# CH1_ANALOG.net
KiCad netlist of a schematic drawn in Altium Designer
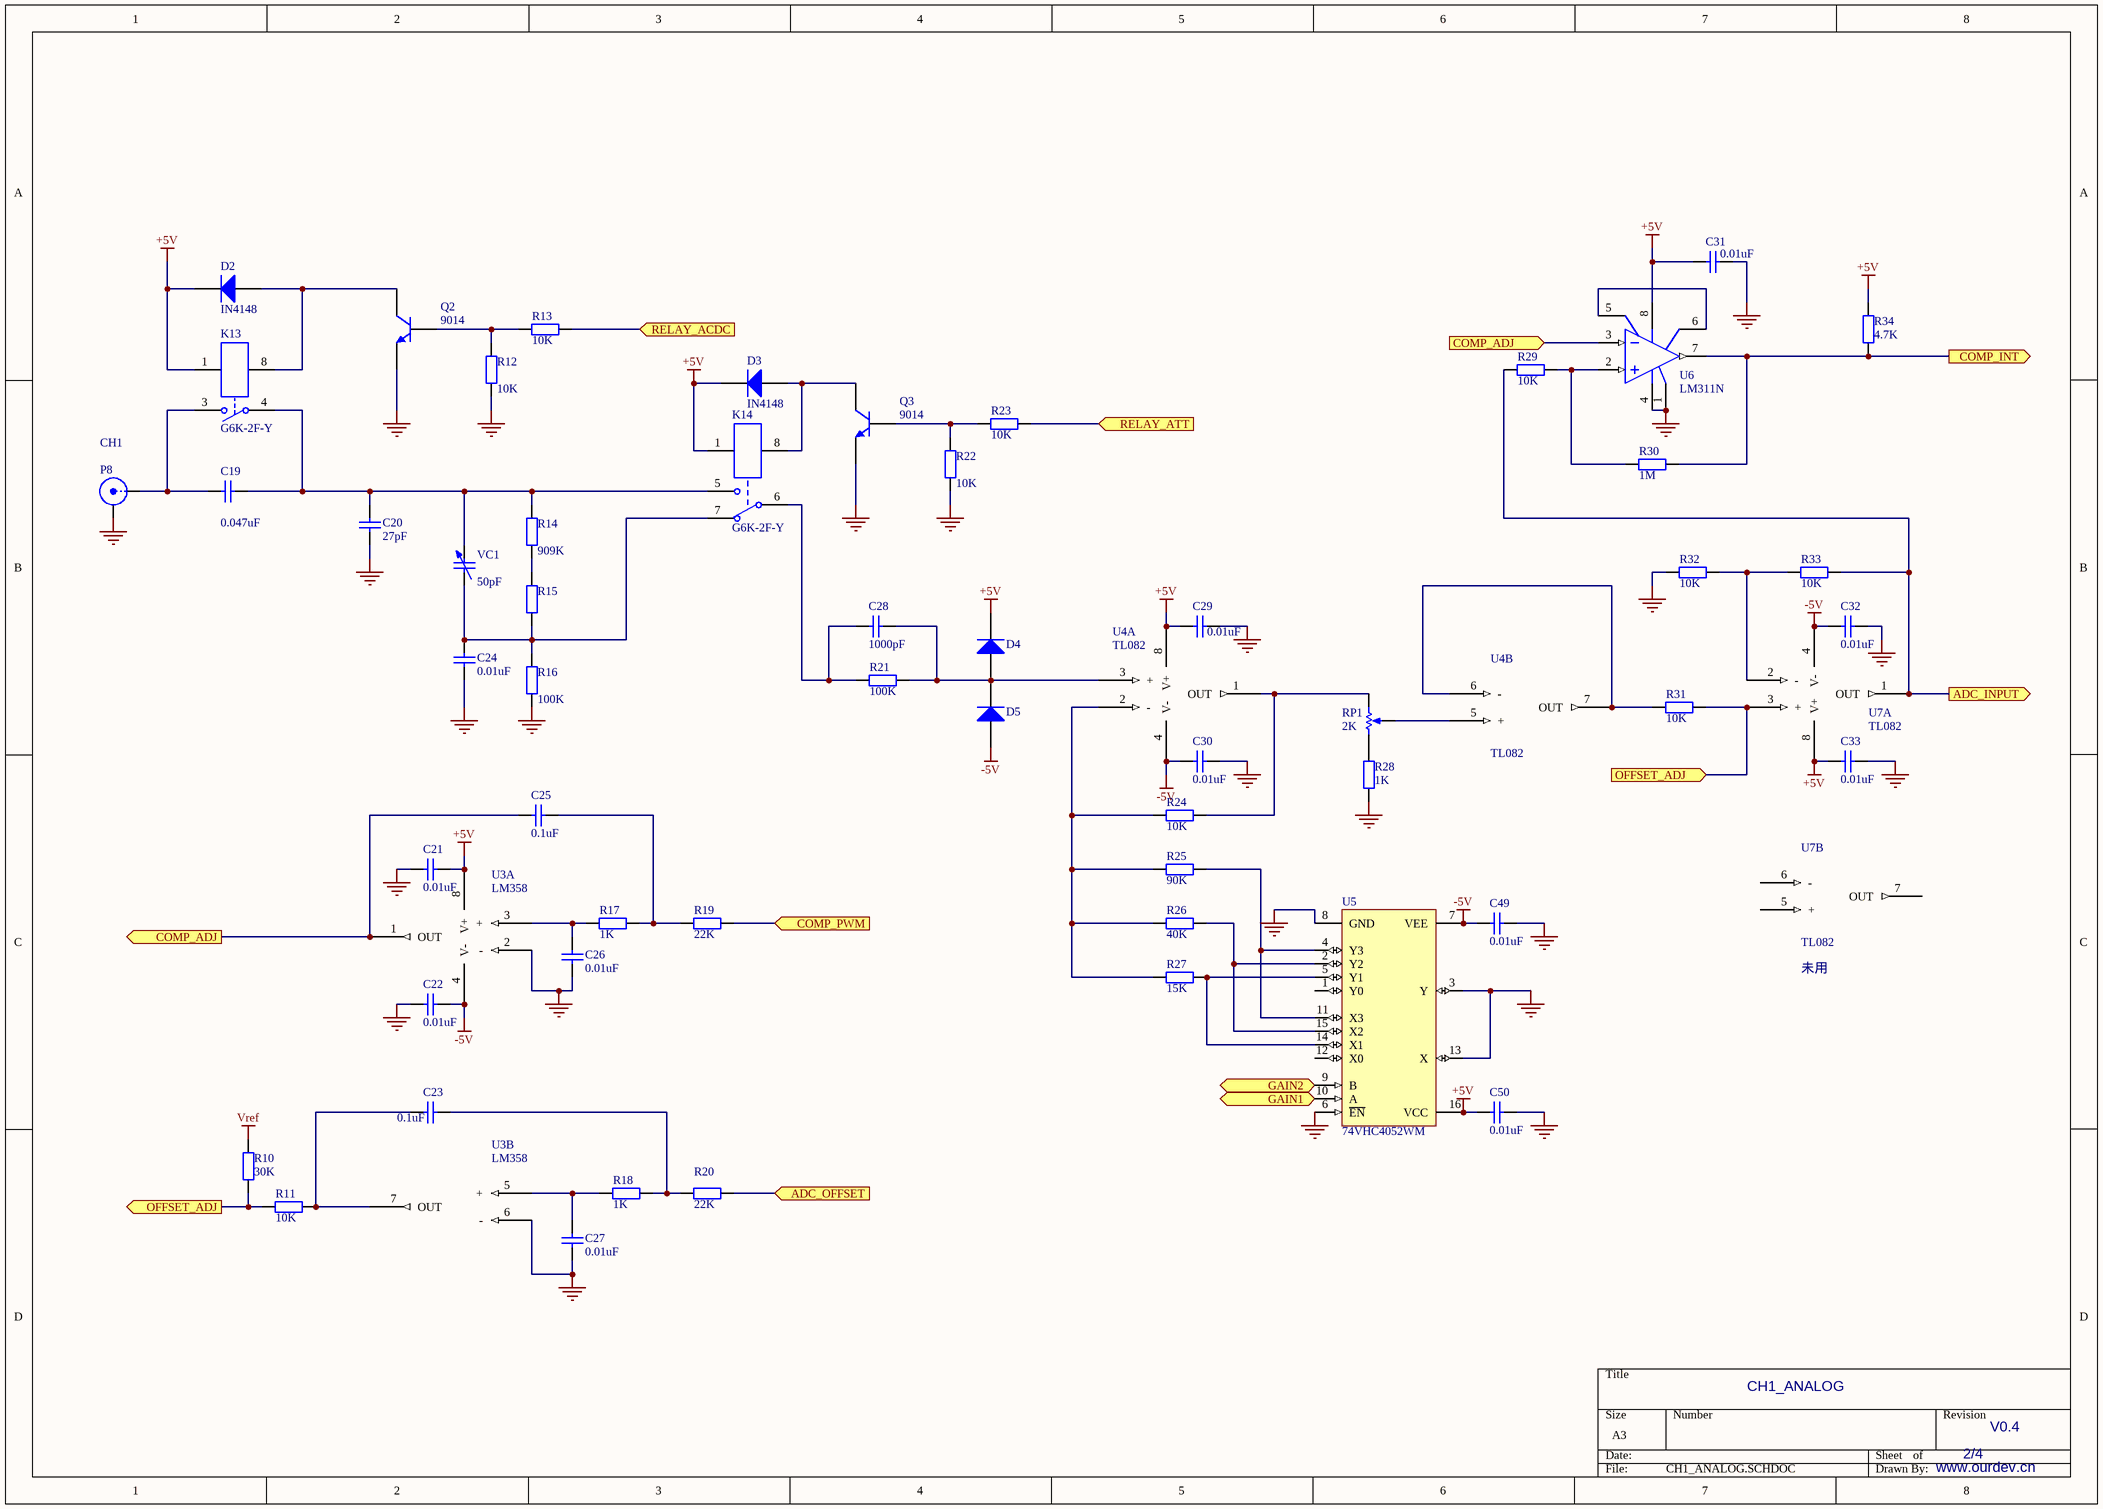
[diagram p0: CH1_ANALOG.SCHDOC]

(export (version "E")
  (design (tool "Eeschema 10.0.6"))
  (components
    (comp (ref "C19")
      (value "0.047uF")
      (footprint "CBB CAP")
      (description "Capacitor")
      (fields (field (name "Comment") "Cap") (field (name "PUBLISHER") "Altium Limited"))
      (libsource (lib "Miscellaneous Devices") (part "Cap"))
    )
    (comp (ref "C20")
      (value "27pF")
      (footprint "CO2")
      (description "Capacitor")
      (fields (field (name "Comment") "Cap") (field (name "PUBLISHER") "Altium Limited"))
      (libsource (lib "Miscellaneous Devices") (part "Cap"))
    )
    (comp (ref "C21")
      (value "0.01uF")
      (footprint "CC2012-0805")
      (description "Capacitor")
      (fields (field (name "Comment") "Cap") (field (name "PUBLISHER") "Altium Limited"))
      (libsource (lib "Miscellaneous Devices") (part "Cap"))
    )
    (comp (ref "C22")
      (value "0.01uF")
      (footprint "CC2012-0805")
      (description "Capacitor")
      (fields (field (name "Comment") "Cap") (field (name "PUBLISHER") "Altium Limited"))
      (libsource (lib "Miscellaneous Devices") (part "Cap"))
    )
    (comp (ref "C23")
      (value "0.1uF")
      (footprint "CC2012-0805")
      (description "Capacitor")
      (fields (field (name "Comment") "Cap") (field (name "PUBLISHER") "Altium Limited"))
      (libsource (lib "Miscellaneous Devices") (part "Cap"))
    )
    (comp (ref "C24")
      (value "0.01uF")
      (footprint "C1206")
      (description "Capacitor")
      (fields (field (name "Comment") "Cap") (field (name "PUBLISHER") "Altium Limited"))
      (libsource (lib "Miscellaneous Devices") (part "Cap"))
    )
    (comp (ref "C25")
      (value "0.1uF")
      (footprint "CC2012-0805")
      (description "Capacitor")
      (fields (field (name "Comment") "Cap") (field (name "PUBLISHER") "Altium Limited"))
      (libsource (lib "Miscellaneous Devices") (part "Cap"))
    )
    (comp (ref "C26")
      (value "0.01uF")
      (footprint "CC2012-0805")
      (description "Capacitor")
      (fields (field (name "Comment") "Cap") (field (name "PUBLISHER") "Altium Limited"))
      (libsource (lib "Miscellaneous Devices") (part "Cap"))
    )
    (comp (ref "C27")
      (value "0.01uF")
      (footprint "CC2012-0805")
      (description "Capacitor")
      (fields (field (name "Comment") "Cap") (field (name "PUBLISHER") "Altium Limited"))
      (libsource (lib "Miscellaneous Devices") (part "Cap"))
    )
    (comp (ref "C28")
      (value "1000pF")
      (footprint "CC2012-0805")
      (description "Capacitor")
      (fields (field (name "Comment") "Cap") (field (name "PUBLISHER") "Altium Limited"))
      (libsource (lib "Miscellaneous Devices") (part "Cap"))
    )
    (comp (ref "C29")
      (value "0.01uF")
      (footprint "CC2012-0805")
      (description "Capacitor")
      (fields (field (name "Comment") "Cap") (field (name "PUBLISHER") "Altium Limited"))
      (libsource (lib "Miscellaneous Devices") (part "Cap"))
    )
    (comp (ref "C30")
      (value "0.01uF")
      (footprint "CC2012-0805")
      (description "Capacitor")
      (fields (field (name "Comment") "Cap") (field (name "PUBLISHER") "Altium Limited"))
      (libsource (lib "Miscellaneous Devices") (part "Cap"))
    )
    (comp (ref "C31")
      (value "0.01uF")
      (footprint "CC2012-0805")
      (description "Capacitor")
      (fields (field (name "Comment") "Cap") (field (name "PUBLISHER") "Altium Limited"))
      (libsource (lib "Miscellaneous Devices") (part "Cap"))
    )
    (comp (ref "C32")
      (value "0.01uF")
      (footprint "CC2012-0805")
      (description "Capacitor")
      (fields (field (name "Comment") "Cap") (field (name "PUBLISHER") "Altium Limited"))
      (libsource (lib "Miscellaneous Devices") (part "Cap"))
    )
    (comp (ref "C33")
      (value "0.01uF")
      (footprint "CC2012-0805")
      (description "Capacitor")
      (fields (field (name "Comment") "Cap") (field (name "PUBLISHER") "Altium Limited"))
      (libsource (lib "Miscellaneous Devices") (part "Cap"))
    )
    (comp (ref "C49")
      (value "0.01uF")
      (footprint "CC2012-0805")
      (description "Capacitor")
      (fields (field (name "Comment") "Cap") (field (name "PUBLISHER") "Altium Limited"))
      (libsource (lib "Miscellaneous Devices") (part "Cap"))
    )
    (comp (ref "C50")
      (value "0.01uF")
      (footprint "CC2012-0805")
      (description "Capacitor")
      (fields (field (name "Comment") "Cap") (field (name "PUBLISHER") "Altium Limited"))
      (libsource (lib "Miscellaneous Devices") (part "Cap"))
    )
    (comp (ref "D2")
      (value "IN4148")
      (footprint "DIODE")
      (description "Default Diode")
      (fields (field (name "PUBLISHER") "Altium Limited"))
      (libsource (lib "Miscellaneous Devices") (part "Diode"))
    )
    (comp (ref "D3")
      (value "IN4148")
      (footprint "DIODE")
      (description "Default Diode")
      (fields (field (name "PUBLISHER") "Altium Limited"))
      (libsource (lib "Miscellaneous Devices") (part "Diode"))
    )
    (comp (ref "D4")
      (value "Diode")
      (footprint "SMA")
      (description "Default Diode")
      (fields (field (name "PUBLISHER") "Altium Limited"))
      (libsource (lib "Miscellaneous Devices") (part "Diode"))
    )
    (comp (ref "D5")
      (value "Diode")
      (footprint "SMA")
      (description "Default Diode")
      (fields (field (name "PUBLISHER") "Altium Limited"))
      (libsource (lib "Miscellaneous Devices") (part "Diode"))
    )
    (comp (ref "K13")
      (value "G6K-2F-Y")
      (footprint "G6K-2F-Y")
      (description "Single-Pole Single-Throw Relay")
      (fields (field (name "PUBLISHER") "Altium Limited"))
      (libsource (lib "Miscellaneous Devices") (part "Relay-SPST"))
    )
    (comp (ref "K14")
      (value "G6K-2F-Y")
      (footprint "G6K-2F-Y")
      (description "Single-Pole Dual-Throw Relay")
      (fields (field (name "PUBLISHER") "Altium Limited"))
      (libsource (lib "Miscellaneous Devices") (part "Relay-SPDT"))
    )
    (comp (ref "P8")
      (value "CH1")
      (footprint "BNC_RA CON")
      (description "BNC Elbow Connector")
      (fields (field (name "PUBLISHER") "Altium Limited"))
      (libsource (lib "Miscellaneous Connectors") (part "BNC"))
    )
    (comp (ref "Q2")
      (value "9014")
      (footprint "SOT-23")
      (description "NPN Bipolar Transistor")
      (fields (field (name "PUBLISHER") "Altium Limited"))
      (libsource (lib "Miscellaneous Devices") (part "NPN"))
    )
    (comp (ref "Q3")
      (value "9014")
      (footprint "SOT-23")
      (description "NPN Bipolar Transistor")
      (fields (field (name "PUBLISHER") "Altium Limited"))
      (libsource (lib "Miscellaneous Devices") (part "NPN"))
    )
    (comp (ref "R10")
      (value "30K")
      (footprint "CR2012-0805")
      (description "Resistor")
      (fields (field (name "Comment") "Res2") (field (name "PUBLISHER") "Altium Limited"))
      (libsource (lib "Miscellaneous Devices") (part "Res2"))
    )
    (comp (ref "R11")
      (value "10K")
      (footprint "CR2012-0805")
      (description "Resistor")
      (fields (field (name "Comment") "Res2") (field (name "PUBLISHER") "Altium Limited"))
      (libsource (lib "") (part "Res2_2"))
    )
    (comp (ref "R12")
      (value "10K")
      (footprint "CR2012-0805")
      (description "Resistor")
      (fields (field (name "Comment") "Res2") (field (name "PUBLISHER") "Altium Limited"))
      (libsource (lib "Miscellaneous Devices") (part "Res2"))
    )
    (comp (ref "R13")
      (value "10K")
      (footprint "CR2012-0805")
      (description "Resistor")
      (fields (field (name "Comment") "Res2") (field (name "PUBLISHER") "Altium Limited"))
      (libsource (lib "") (part "Res2_1"))
    )
    (comp (ref "R14")
      (value "909K")
      (footprint "R-1206")
      (description "Resistor")
      (fields (field (name "Comment") "Res2") (field (name "PUBLISHER") "Altium Limited"))
      (libsource (lib "Miscellaneous Devices") (part "Res2"))
    )
    (comp (ref "R15")
      (value "Res2")
      (footprint "R-1206")
      (description "Resistor")
      (fields (field (name "PUBLISHER") "Altium Limited"))
      (libsource (lib "Miscellaneous Devices") (part "Res2"))
    )
    (comp (ref "R16")
      (value "100K")
      (footprint "R-1206")
      (description "Resistor")
      (fields (field (name "Comment") "Res2") (field (name "PUBLISHER") "Altium Limited"))
      (libsource (lib "Miscellaneous Devices") (part "Res2"))
    )
    (comp (ref "R17")
      (value "1K")
      (footprint "CR2012-0805")
      (description "Resistor")
      (fields (field (name "Comment") "Res2") (field (name "PUBLISHER") "Altium Limited"))
      (libsource (lib "Miscellaneous Devices") (part "Res2"))
    )
    (comp (ref "R18")
      (value "1K")
      (footprint "CR2012-0805")
      (description "Resistor")
      (fields (field (name "Comment") "Res2") (field (name "PUBLISHER") "Altium Limited"))
      (libsource (lib "") (part "Res2_2"))
    )
    (comp (ref "R19")
      (value "22K")
      (footprint "CR2012-0805")
      (description "Resistor")
      (fields (field (name "Comment") "Res2") (field (name "PUBLISHER") "Altium Limited"))
      (libsource (lib "Miscellaneous Devices") (part "Res2"))
    )
    (comp (ref "R20")
      (value "22K")
      (footprint "CR2012-0805")
      (description "Resistor")
      (fields (field (name "Comment") "Res2") (field (name "PUBLISHER") "Altium Limited"))
      (libsource (lib "") (part "Res2_2"))
    )
    (comp (ref "R21")
      (value "100K")
      (footprint "CR2012-0805")
      (description "Resistor")
      (fields (field (name "Comment") "Res2") (field (name "PUBLISHER") "Altium Limited"))
      (libsource (lib "") (part "Res2_1"))
    )
    (comp (ref "R22")
      (value "10K")
      (footprint "CR2012-0805")
      (description "Resistor")
      (fields (field (name "Comment") "Res2") (field (name "PUBLISHER") "Altium Limited"))
      (libsource (lib "Miscellaneous Devices") (part "Res2"))
    )
    (comp (ref "R23")
      (value "10K")
      (footprint "CR2012-0805")
      (description "Resistor")
      (fields (field (name "Comment") "Res2") (field (name "PUBLISHER") "Altium Limited"))
      (libsource (lib "") (part "Res2_1"))
    )
    (comp (ref "R24")
      (value "10K")
      (footprint "CR2012-0805")
      (description "Resistor")
      (fields (field (name "Comment") "Res2") (field (name "PUBLISHER") "Altium Limited"))
      (libsource (lib "") (part "Res2_1"))
    )
    (comp (ref "R25")
      (value "90K")
      (footprint "CR2012-0805")
      (description "Resistor")
      (fields (field (name "Comment") "Res2") (field (name "PUBLISHER") "Altium Limited"))
      (libsource (lib "") (part "Res2_1"))
    )
    (comp (ref "R26")
      (value "40K")
      (footprint "CR2012-0805")
      (description "Resistor")
      (fields (field (name "Comment") "Res2") (field (name "PUBLISHER") "Altium Limited"))
      (libsource (lib "") (part "Res2_1"))
    )
    (comp (ref "R27")
      (value "15K")
      (footprint "CR2012-0805")
      (description "Resistor")
      (fields (field (name "Comment") "Res2") (field (name "PUBLISHER") "Altium Limited"))
      (libsource (lib "") (part "Res2_1"))
    )
    (comp (ref "R28")
      (value "1K")
      (footprint "CR2012-0805")
      (description "Resistor")
      (fields (field (name "Comment") "Res2") (field (name "PUBLISHER") "Altium Limited"))
      (libsource (lib "") (part "Res2_3"))
    )
    (comp (ref "R29")
      (value "10K")
      (footprint "CR2012-0805")
      (description "Resistor")
      (fields (field (name "Comment") "Res2") (field (name "PUBLISHER") "Altium Limited"))
      (libsource (lib "Miscellaneous Devices") (part "Res2"))
    )
    (comp (ref "R30")
      (value "1M")
      (footprint "CR2012-0805")
      (description "Resistor")
      (fields (field (name "Comment") "Res2") (field (name "PUBLISHER") "Altium Limited"))
      (libsource (lib "Miscellaneous Devices") (part "Res2"))
    )
    (comp (ref "R31")
      (value "10K")
      (footprint "CR2012-0805")
      (description "Resistor")
      (fields (field (name "Comment") "Res2") (field (name "PUBLISHER") "Altium Limited"))
      (libsource (lib "") (part "Res2_1"))
    )
    (comp (ref "R32")
      (value "10K")
      (footprint "CR2012-0805")
      (description "Resistor")
      (fields (field (name "Comment") "Res2") (field (name "PUBLISHER") "Altium Limited"))
      (libsource (lib "") (part "Res2_2"))
    )
    (comp (ref "R33")
      (value "10K")
      (footprint "CR2012-0805")
      (description "Resistor")
      (fields (field (name "Comment") "Res2") (field (name "PUBLISHER") "Altium Limited"))
      (libsource (lib "") (part "Res2_1"))
    )
    (comp (ref "R34")
      (value "4.7K")
      (footprint "CR2012-0805")
      (description "Resistor")
      (fields (field (name "Comment") "Res2") (field (name "PUBLISHER") "Altium Limited"))
      (libsource (lib "") (part "Res2_1"))
    )
    (comp (ref "RP1")
      (value "2K")
      (footprint "VR")
      (description "Potentiometer")
      (fields (field (name "Comment") "RPot") (field (name "PUBLISHER") "Altium Limited"))
      (libsource (lib "Miscellaneous Devices") (part "RPot"))
    )
    (comp (ref "U3") (value "LM358") (footprint "SO-8") (libsource (lib "LM358") (part "LM358")))
    (comp (ref "U4") (value "TL082") (footprint "SO-8") (libsource (lib "TL082") (part "TL082")))
    (comp (ref "U5")
      (value "74VHC4052WM")
      (footprint "SO-16")
      (description "Dual 4-Channel Analog Multiplexer")
      (fields (field (name "PUBLISHER") "Altium Limited"))
      (libsource (lib "FSC Logic Multiplexer") (part "74VHC4052WM"))
    )
    (comp (ref "U6")
      (value "LM311N")
      (footprint "SO-8")
      (description "High-Performance Voltage Comparator")
      (fields (field (name "PUBLISHER") "Altium Limited"))
      (libsource (lib "Motorola Analog Comparator") (part "LM311N"))
    )
    (comp (ref "U7") (value "TL082") (footprint "SO-8") (libsource (lib "TL082") (part "TL082")))
    (comp (ref "VC1")
      (value "50pF")
      (footprint "C1206")
      (description "Variable or Adjustable Capacitor")
      (fields (field (name "Comment") "Cap Var") (field (name "PUBLISHER") "Altium Limited"))
      (libsource (lib "Miscellaneous Devices") (part "Cap Var"))
    )
  )
  (nets
    (net (code "1") (name "+5V") (class "Default")
      (node (ref "C21") (pin "2") (pinfunction "2_2") (pintype "passive"))
      (node (ref "C29") (pin "2") (pinfunction "2_2") (pintype "passive"))
      (node (ref "C31") (pin "2") (pinfunction "2_2") (pintype "passive"))
      (node (ref "C33") (pin "2") (pinfunction "2_2") (pintype "passive"))
      (node (ref "C50") (pin "2") (pinfunction "2_2") (pintype "passive"))
      (node (ref "D2") (pin "2") (pinfunction "K_2") (pintype "passive"))
      (node (ref "D3") (pin "2") (pinfunction "K_2") (pintype "passive"))
      (node (ref "D4") (pin "2") (pinfunction "K_2") (pintype "passive"))
      (node (ref "K13") (pin "1") (pinfunction "1_1") (pintype "passive"))
      (node (ref "K14") (pin "1") (pinfunction "1_1") (pintype "passive"))
      (node (ref "R34") (pin "1") (pinfunction "1_1") (pintype "passive"))
      (node (ref "U3") (pin "8") (pinfunction "V+_8") (pintype "passive"))
      (node (ref "U4") (pin "8") (pinfunction "V+_8") (pintype "passive"))
      (node (ref "U5") (pin "16") (pinfunction "VCC_16") (pintype "power_in"))
      (node (ref "U6") (pin "8") (pinfunction "V+_8") (pintype "power_in"))
      (node (ref "U7") (pin "8") (pinfunction "V+_8") (pintype "passive"))
    )
    (net (code "2") (name "-5V") (class "Default")
      (node (ref "C22") (pin "2") (pinfunction "2_2") (pintype "passive"))
      (node (ref "C30") (pin "2") (pinfunction "2_2") (pintype "passive"))
      (node (ref "C32") (pin "2") (pinfunction "2_2") (pintype "passive"))
      (node (ref "C49") (pin "2") (pinfunction "2_2") (pintype "passive"))
      (node (ref "D5") (pin "1") (pinfunction "A_1") (pintype "passive"))
      (node (ref "U3") (pin "4") (pinfunction "V-_4") (pintype "passive"))
      (node (ref "U4") (pin "4") (pinfunction "V-_4") (pintype "passive"))
      (node (ref "U5") (pin "7") (pinfunction "VEE_7") (pintype "power_in"))
      (node (ref "U7") (pin "4") (pinfunction "V-_4") (pintype "passive"))
    )
    (net (code "3") (name "/ADC_INPUT") (class "Default")
      (node (ref "R29") (pin "1") (pinfunction "1_1") (pintype "passive"))
      (node (ref "R33") (pin "1") (pinfunction "1_1") (pintype "passive"))
      (node (ref "U7") (pin "1") (pinfunction "OUT_1") (pintype "output"))
    )
    (net (code "4") (name "/ADC_OFFSET") (class "Default")
      (node (ref "R20") (pin "2") (pinfunction "2_2") (pintype "passive"))
    )
    (net (code "5") (name "/COMP_ADJ") (class "Default")
      (node (ref "C25") (pin "1") (pinfunction "1_1") (pintype "passive"))
      (node (ref "U3") (pin "1") (pinfunction "OUT_1") (pintype "output"))
      (node (ref "U6") (pin "3") (pinfunction "IN-_3") (pintype "input"))
    )
    (net (code "6") (name "/COMP_INT") (class "Default")
      (node (ref "R30") (pin "2") (pinfunction "2_2") (pintype "passive"))
      (node (ref "R34") (pin "2") (pinfunction "2_2") (pintype "passive"))
      (node (ref "U6") (pin "7") (pinfunction "OUT_7") (pintype "output"))
    )
    (net (code "7") (name "/COMP_PWM") (class "Default")
      (node (ref "R19") (pin "2") (pinfunction "2_2") (pintype "passive"))
    )
    (net (code "8") (name "/GAIN1") (class "Default")
      (node (ref "U5") (pin "10") (pinfunction "A_10") (pintype "input"))
    )
    (net (code "9") (name "/GAIN2") (class "Default")
      (node (ref "U5") (pin "9") (pinfunction "B_9") (pintype "input"))
    )
    (net (code "10") (name "/OFFSET_ADJ") (class "Default")
      (node (ref "R10") (pin "1") (pinfunction "1_1") (pintype "passive"))
      (node (ref "R11") (pin "1") (pinfunction "1_1") (pintype "passive"))
      (node (ref "R31") (pin "1") (pinfunction "1_1") (pintype "passive"))
      (node (ref "U7") (pin "3") (pinfunction "+_3") (pintype "input"))
    )
    (net (code "11") (name "/RELAY_ACDC") (class "Default")
      (node (ref "R13") (pin "1") (pinfunction "1_1") (pintype "passive"))
    )
    (net (code "12") (name "/RELAY_ATT") (class "Default")
      (node (ref "R23") (pin "1") (pinfunction "1_1") (pintype "passive"))
    )
    (net (code "13") (name "GND") (class "Default")
      (node (ref "C20") (pin "1") (pinfunction "1_1") (pintype "passive"))
      (node (ref "C21") (pin "1") (pinfunction "1_1") (pintype "passive"))
      (node (ref "C22") (pin "1") (pinfunction "1_1") (pintype "passive"))
      (node (ref "C24") (pin "1") (pinfunction "1_1") (pintype "passive"))
      (node (ref "C26") (pin "1") (pinfunction "1_1") (pintype "passive"))
      (node (ref "C27") (pin "1") (pinfunction "1_1") (pintype "passive"))
      (node (ref "C29") (pin "1") (pinfunction "1_1") (pintype "passive"))
      (node (ref "C30") (pin "1") (pinfunction "1_1") (pintype "passive"))
      (node (ref "C31") (pin "1") (pinfunction "1_1") (pintype "passive"))
      (node (ref "C32") (pin "1") (pinfunction "1_1") (pintype "passive"))
      (node (ref "C33") (pin "1") (pinfunction "1_1") (pintype "passive"))
      (node (ref "C49") (pin "1") (pinfunction "1_1") (pintype "passive"))
      (node (ref "C50") (pin "1") (pinfunction "1_1") (pintype "passive"))
      (node (ref "P8") (pin "2") (pinfunction "Y_2") (pintype "passive"))
      (node (ref "Q2") (pin "2") (pinfunction "E_2") (pintype "passive"))
      (node (ref "Q3") (pin "2") (pinfunction "E_2") (pintype "passive"))
      (node (ref "R12") (pin "1") (pinfunction "1_1") (pintype "passive"))
      (node (ref "R16") (pin "1") (pinfunction "1_1") (pintype "passive"))
      (node (ref "R22") (pin "1") (pinfunction "1_1") (pintype "passive"))
      (node (ref "R28") (pin "2") (pinfunction "2_2") (pintype "passive"))
      (node (ref "R32") (pin "1") (pinfunction "1_1") (pintype "passive"))
      (node (ref "U3") (pin "2") (pinfunction "-_2") (pintype "input"))
      (node (ref "U3") (pin "6") (pinfunction "-_6") (pintype "input"))
      (node (ref "U5") (pin "13") (pinfunction "X_13") (pintype "bidirectional"))
      (node (ref "U5") (pin "3") (pinfunction "Y_3") (pintype "bidirectional"))
      (node (ref "U5") (pin "6") (pinfunction "~{EN}_6") (pintype "input"))
      (node (ref "U5") (pin "8") (pinfunction "GND_8") (pintype "power_in"))
      (node (ref "U6") (pin "1") (pinfunction "GND_1") (pintype "power_in"))
      (node (ref "U6") (pin "4") (pinfunction "V-_4") (pintype "power_in"))
    )
    (net (code "14") (name "Net-(C19-Pad2)") (class "Default")
      (node (ref "C19") (pin "2") (pinfunction "2_2") (pintype "passive"))
      (node (ref "C20") (pin "2") (pinfunction "2_2") (pintype "passive"))
      (node (ref "K13") (pin "4") (pinfunction "4_4") (pintype "passive"))
      (node (ref "K14") (pin "5") (pinfunction "5_5") (pintype "passive"))
      (node (ref "R14") (pin "2") (pinfunction "2_2") (pintype "passive"))
      (node (ref "VC1") (pin "2") (pinfunction "2_2") (pintype "passive"))
    )
    (net (code "15") (name "Net-(C23-Pad2)") (class "Default")
      (node (ref "C23") (pin "2") (pinfunction "2_2") (pintype "passive"))
      (node (ref "R18") (pin "2") (pinfunction "2_2") (pintype "passive"))
      (node (ref "R20") (pin "1") (pinfunction "1_1") (pintype "passive"))
    )
    (net (code "16") (name "Net-(C24-Pad2)") (class "Default")
      (node (ref "C24") (pin "2") (pinfunction "2_2") (pintype "passive"))
      (node (ref "K14") (pin "7") (pinfunction "7_7") (pintype "passive"))
      (node (ref "R15") (pin "1") (pinfunction "1_1") (pintype "passive"))
      (node (ref "R16") (pin "2") (pinfunction "2_2") (pintype "passive"))
      (node (ref "VC1") (pin "1") (pinfunction "1_1") (pintype "passive"))
    )
    (net (code "17") (name "Net-(C25-Pad2)") (class "Default")
      (node (ref "C25") (pin "2") (pinfunction "2_2") (pintype "passive"))
      (node (ref "R17") (pin "2") (pinfunction "2_2") (pintype "passive"))
      (node (ref "R19") (pin "1") (pinfunction "1_1") (pintype "passive"))
    )
    (net (code "18") (name "Net-(C28-Pad2)") (class "Default")
      (node (ref "C28") (pin "2") (pinfunction "2_2") (pintype "passive"))
      (node (ref "K14") (pin "6") (pinfunction "6_6") (pintype "passive"))
      (node (ref "R21") (pin "2") (pinfunction "2_2") (pintype "passive"))
    )
    (net (code "19") (name "Net-(D2-A)") (class "Default")
      (node (ref "D2") (pin "1") (pinfunction "A_1") (pintype "passive"))
      (node (ref "K13") (pin "8") (pinfunction "8_8") (pintype "passive"))
      (node (ref "Q2") (pin "3") (pinfunction "C_3") (pintype "passive"))
    )
    (net (code "20") (name "Net-(D3-A)") (class "Default")
      (node (ref "D3") (pin "1") (pinfunction "A_1") (pintype "passive"))
      (node (ref "K14") (pin "8") (pinfunction "8_8") (pintype "passive"))
      (node (ref "Q3") (pin "3") (pinfunction "C_3") (pintype "passive"))
    )
    (net (code "21") (name "Net-(D4-A)") (class "Default")
      (node (ref "C28") (pin "1") (pinfunction "1_1") (pintype "passive"))
      (node (ref "D4") (pin "1") (pinfunction "A_1") (pintype "passive"))
      (node (ref "D5") (pin "2") (pinfunction "K_2") (pintype "passive"))
      (node (ref "R21") (pin "1") (pinfunction "1_1") (pintype "passive"))
      (node (ref "U4") (pin "3") (pinfunction "+_3") (pintype "input"))
    )
    (net (code "22") (name "Net-(P8-X)") (class "Default")
      (node (ref "C19") (pin "1") (pinfunction "1_1") (pintype "passive"))
      (node (ref "K13") (pin "3") (pinfunction "3_3") (pintype "passive"))
      (node (ref "P8") (pin "1") (pinfunction "X_1") (pintype "passive"))
    )
    (net (code "23") (name "Net-(Q2-B)") (class "Default")
      (node (ref "Q2") (pin "1") (pinfunction "B_1") (pintype "passive"))
      (node (ref "R12") (pin "2") (pinfunction "2_2") (pintype "passive"))
      (node (ref "R13") (pin "2") (pinfunction "2_2") (pintype "passive"))
    )
    (net (code "24") (name "Net-(Q3-B)") (class "Default")
      (node (ref "Q3") (pin "1") (pinfunction "B_1") (pintype "passive"))
      (node (ref "R22") (pin "2") (pinfunction "2_2") (pintype "passive"))
      (node (ref "R23") (pin "2") (pinfunction "2_2") (pintype "passive"))
    )
    (net (code "25") (name "Net-(R14-Pad1)") (class "Default")
      (node (ref "R14") (pin "1") (pinfunction "1_1") (pintype "passive"))
      (node (ref "R15") (pin "2") (pinfunction "2_2") (pintype "passive"))
    )
    (net (code "26") (name "Net-(RP1-BOT)") (class "Default")
      (node (ref "R24") (pin "1") (pinfunction "1_1") (pintype "passive"))
      (node (ref "RP1") (pin "3") (pinfunction "BOT_3") (pintype "passive"))
      (node (ref "U4") (pin "1") (pinfunction "OUT_1") (pintype "output"))
    )
    (net (code "27") (name "Net-(RP1-TAP)") (class "Default")
      (node (ref "RP1") (pin "2") (pinfunction "TAP_2") (pintype "passive"))
      (node (ref "U4") (pin "5") (pinfunction "+_5") (pintype "input"))
    )
    (net (code "28") (name "Net-(RP1-TOP)") (class "Default")
      (node (ref "R28") (pin "1") (pinfunction "1_1") (pintype "passive"))
      (node (ref "RP1") (pin "1") (pinfunction "TOP_1") (pintype "passive"))
    )
    (net (code "29") (name "Net-(U3A-+)") (class "Default")
      (node (ref "C26") (pin "2") (pinfunction "2_2") (pintype "passive"))
      (node (ref "R17") (pin "1") (pinfunction "1_1") (pintype "passive"))
      (node (ref "U3") (pin "3") (pinfunction "+_3") (pintype "input"))
    )
    (net (code "30") (name "Net-(U3B-+)") (class "Default")
      (node (ref "C27") (pin "2") (pinfunction "2_2") (pintype "passive"))
      (node (ref "R18") (pin "1") (pinfunction "1_1") (pintype "passive"))
      (node (ref "U3") (pin "5") (pinfunction "+_5") (pintype "input"))
    )
    (net (code "31") (name "Net-(U3B-OUT)") (class "Default")
      (node (ref "C23") (pin "1") (pinfunction "1_1") (pintype "passive"))
      (node (ref "R11") (pin "2") (pinfunction "2_2") (pintype "passive"))
      (node (ref "U3") (pin "7") (pinfunction "OUT_7") (pintype "output"))
    )
    (net (code "32") (name "Net-(U4A--)") (class "Default")
      (node (ref "R24") (pin "2") (pinfunction "2_2") (pintype "passive"))
      (node (ref "R25") (pin "2") (pinfunction "2_2") (pintype "passive"))
      (node (ref "R26") (pin "2") (pinfunction "2_2") (pintype "passive"))
      (node (ref "R27") (pin "2") (pinfunction "2_2") (pintype "passive"))
      (node (ref "U4") (pin "2") (pinfunction "-_2") (pintype "input"))
    )
    (net (code "33") (name "Net-(U4B--)") (class "Default")
      (node (ref "R31") (pin "2") (pinfunction "2_2") (pintype "passive"))
      (node (ref "U4") (pin "6") (pinfunction "-_6") (pintype "input"))
      (node (ref "U4") (pin "7") (pinfunction "OUT_7") (pintype "output"))
    )
    (net (code "34") (name "Net-(U5-X1)") (class "Default")
      (node (ref "R27") (pin "1") (pinfunction "1_1") (pintype "passive"))
      (node (ref "U5") (pin "14") (pinfunction "X1_14") (pintype "bidirectional"))
      (node (ref "U5") (pin "5") (pinfunction "Y1_5") (pintype "bidirectional"))
    )
    (net (code "35") (name "Net-(U5-X2)") (class "Default")
      (node (ref "R26") (pin "1") (pinfunction "1_1") (pintype "passive"))
      (node (ref "U5") (pin "15") (pinfunction "X2_15") (pintype "bidirectional"))
      (node (ref "U5") (pin "2") (pinfunction "Y2_2") (pintype "bidirectional"))
    )
    (net (code "36") (name "Net-(U5-X3)") (class "Default")
      (node (ref "R25") (pin "1") (pinfunction "1_1") (pintype "passive"))
      (node (ref "U5") (pin "11") (pinfunction "X3_11") (pintype "bidirectional"))
      (node (ref "U5") (pin "4") (pinfunction "Y3_4") (pintype "bidirectional"))
    )
    (net (code "37") (name "Net-(U6-BAL)") (class "Default")
      (node (ref "U6") (pin "5") (pinfunction "BAL_5") (pintype "passive"))
      (node (ref "U6") (pin "6") (pinfunction "BAL/STB_6") (pintype "passive"))
    )
    (net (code "38") (name "Net-(U6-IN+)") (class "Default")
      (node (ref "R29") (pin "2") (pinfunction "2_2") (pintype "passive"))
      (node (ref "R30") (pin "1") (pinfunction "1_1") (pintype "passive"))
      (node (ref "U6") (pin "2") (pinfunction "IN+_2") (pintype "input"))
    )
    (net (code "39") (name "Net-(U7A--)") (class "Default")
      (node (ref "R32") (pin "2") (pinfunction "2_2") (pintype "passive"))
      (node (ref "R33") (pin "2") (pinfunction "2_2") (pintype "passive"))
      (node (ref "U7") (pin "2") (pinfunction "-_2") (pintype "input"))
    )
    (net (code "40") (name "Vref") (class "Default")
      (node (ref "R10") (pin "2") (pinfunction "2_2") (pintype "passive"))
    )
    (net (code "41") (name "unconnected-(U5-X0-Pad12)") (class "Default")
      (node (ref "U5") (pin "12") (pinfunction "X0_12") (pintype "bidirectional"))
    )
    (net (code "42") (name "unconnected-(U5-Y0-Pad1)") (class "Default")
      (node (ref "U5") (pin "1") (pinfunction "Y0_1") (pintype "bidirectional"))
    )
    (net (code "43") (name "unconnected-(U7B-+-Pad5)") (class "Default")
      (node (ref "U7") (pin "5") (pinfunction "+_5") (pintype "input"))
    )
    (net (code "44") (name "unconnected-(U7B---Pad6)") (class "Default")
      (node (ref "U7") (pin "6") (pinfunction "-_6") (pintype "input"))
    )
    (net (code "45") (name "unconnected-(U7B-OUT-Pad7)") (class "Default")
      (node (ref "U7") (pin "7") (pinfunction "OUT_7") (pintype "output"))
    )
  )
)
